# axiom_beta_plugin_module_3xmDP_v1_1_077a.net
KiCad netlist of a schematic drawn in EAGLE
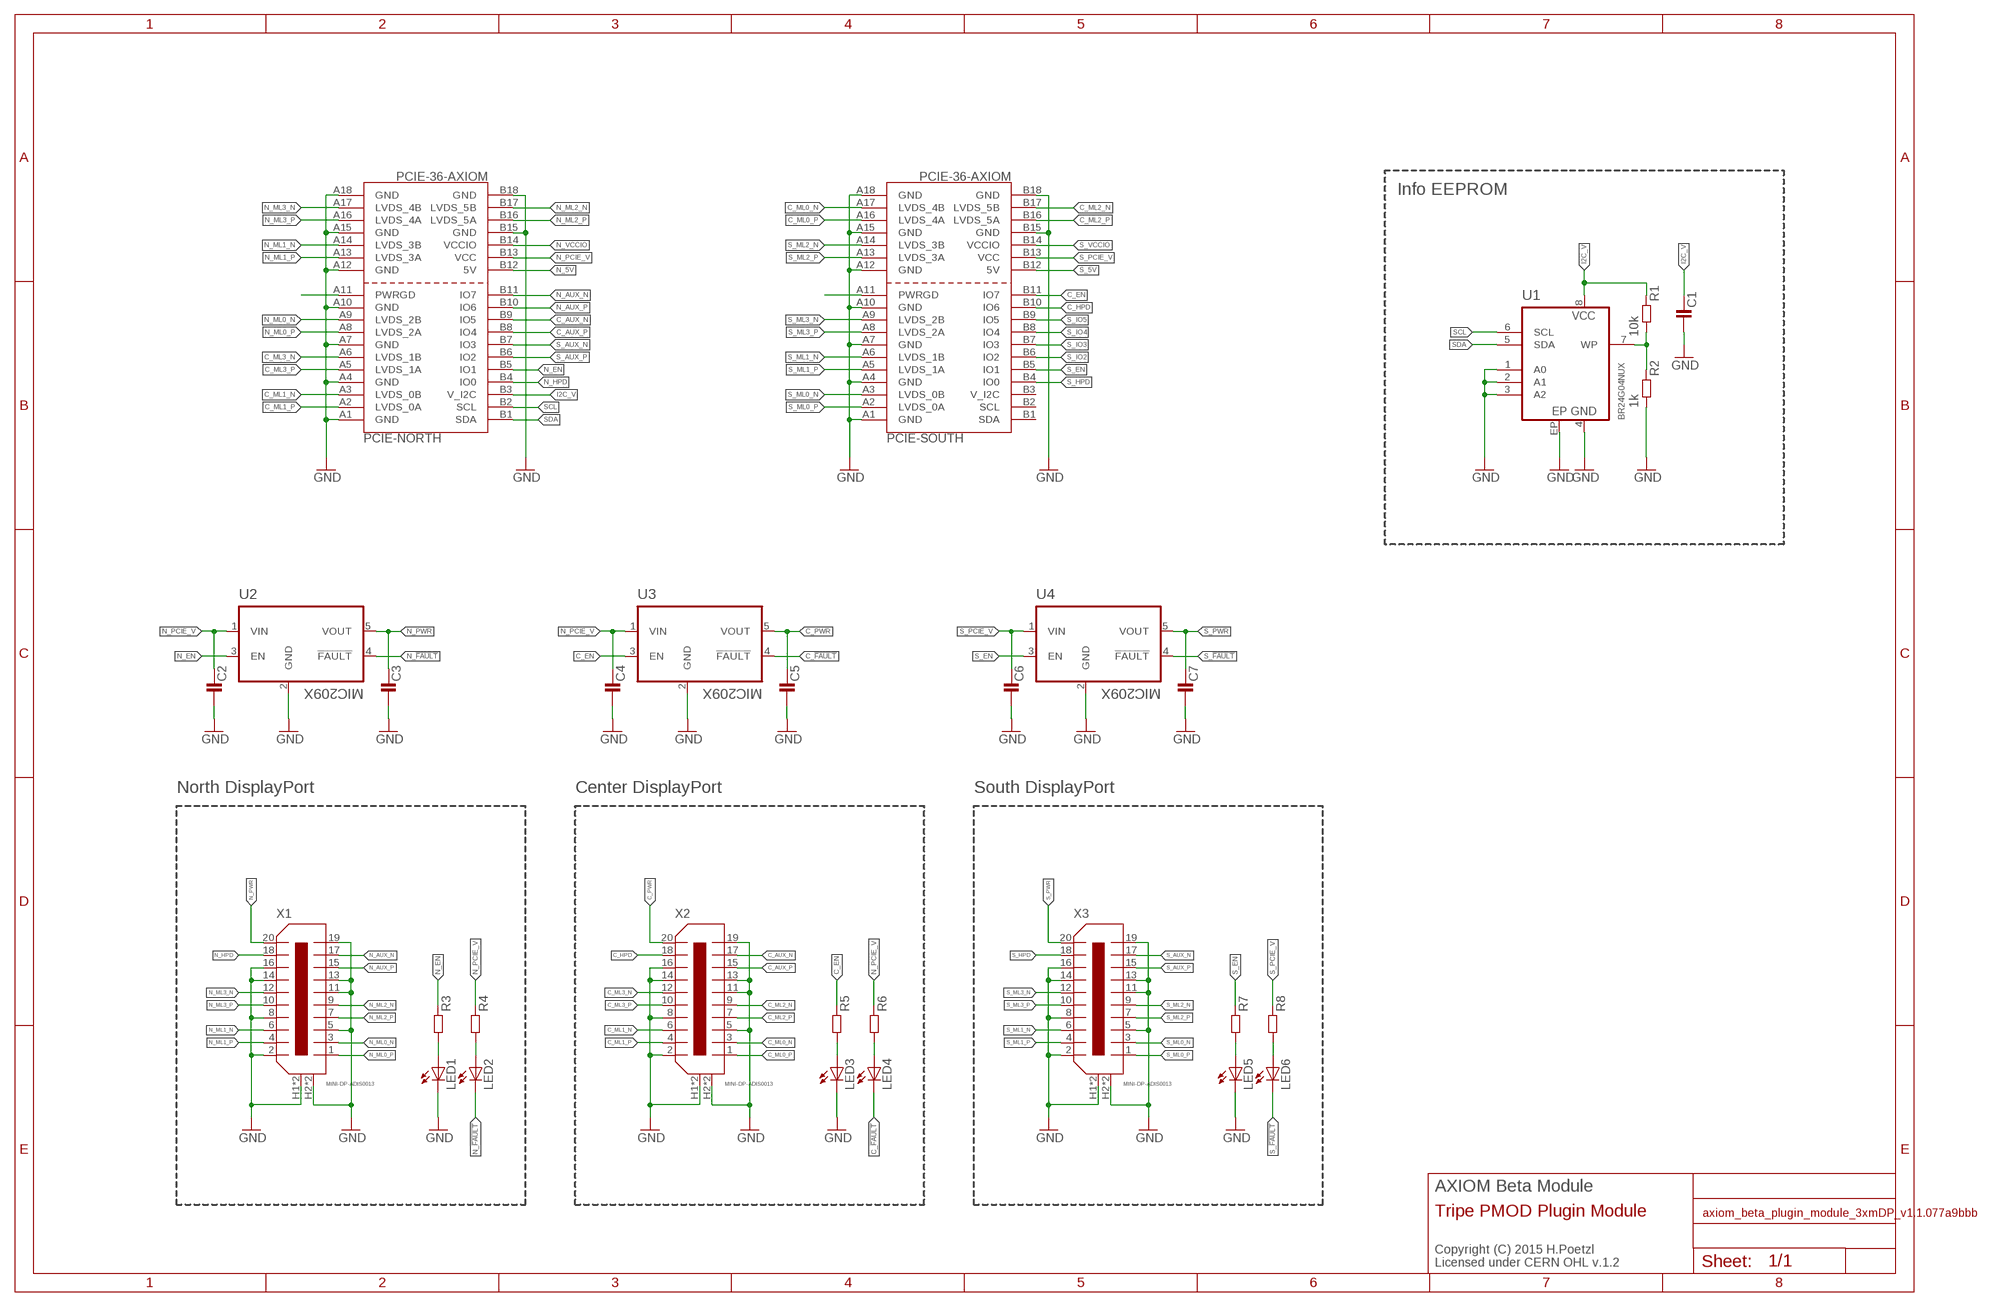
[diagram p0: schematic, sheet 1]

(export (version "E")
  (design (tool "Eeschema 10.0.6"))
  (components
    (comp (ref "C1")
      (value "C0402-B")
      (footprint "eagle-import:0402-B")
      (libsource (lib "eagle-import") (part "C0402-B"))
    )
    (comp (ref "C2")
      (value "C0603-B")
      (footprint "eagle-import:0603-B")
      (libsource (lib "eagle-import") (part "C0603-B"))
    )
    (comp (ref "C3")
      (value "C0603-B")
      (footprint "eagle-import:0603-B")
      (libsource (lib "eagle-import") (part "C0603-B"))
    )
    (comp (ref "C4")
      (value "C0603-B")
      (footprint "eagle-import:0603-B")
      (libsource (lib "eagle-import") (part "C0603-B"))
    )
    (comp (ref "C5")
      (value "C0603-B")
      (footprint "eagle-import:0603-B")
      (libsource (lib "eagle-import") (part "C0603-B"))
    )
    (comp (ref "C6")
      (value "C0603-B")
      (footprint "eagle-import:0603-B")
      (libsource (lib "eagle-import") (part "C0603-B"))
    )
    (comp (ref "C7")
      (value "C0603-B")
      (footprint "eagle-import:0603-B")
      (libsource (lib "eagle-import") (part "C0603-B"))
    )
    (comp (ref "LED1")
      (value "LEDCHIPLED_0603")
      (footprint "eagle-import:CHIPLED_0603")
      (libsource (lib "eagle-import") (part "LEDCHIPLED_0603"))
    )
    (comp (ref "LED2")
      (value "LEDCHIPLED_0603")
      (footprint "eagle-import:CHIPLED_0603")
      (libsource (lib "eagle-import") (part "LEDCHIPLED_0603"))
    )
    (comp (ref "LED3")
      (value "LEDCHIPLED_0603")
      (footprint "eagle-import:CHIPLED_0603")
      (libsource (lib "eagle-import") (part "LEDCHIPLED_0603"))
    )
    (comp (ref "LED4")
      (value "LEDCHIPLED_0603")
      (footprint "eagle-import:CHIPLED_0603")
      (libsource (lib "eagle-import") (part "LEDCHIPLED_0603"))
    )
    (comp (ref "LED5")
      (value "LEDCHIPLED_0603")
      (footprint "eagle-import:CHIPLED_0603")
      (libsource (lib "eagle-import") (part "LEDCHIPLED_0603"))
    )
    (comp (ref "LED6")
      (value "LEDCHIPLED_0603")
      (footprint "eagle-import:CHIPLED_0603")
      (libsource (lib "eagle-import") (part "LEDCHIPLED_0603"))
    )
    (comp (ref "PCIE-NORTH")
      (value "PCIE-36-AXIOM")
      (footprint "eagle-import:PCIE-36-AXIOM")
      (libsource (lib "eagle-import") (part "PCIE-36-AXIOM"))
    )
    (comp (ref "PCIE-SOUTH")
      (value "PCIE-36-AXIOM")
      (footprint "eagle-import:PCIE-36-AXIOM")
      (libsource (lib "eagle-import") (part "PCIE-36-AXIOM"))
    )
    (comp (ref "R1")
      (value "10k")
      (footprint "eagle-import:0402-B")
      (libsource (lib "eagle-import") (part "R0402-B"))
    )
    (comp (ref "R2")
      (value "1k")
      (footprint "eagle-import:0402-B")
      (libsource (lib "eagle-import") (part "R0402-B"))
    )
    (comp (ref "R3")
      (value "R0402-B")
      (footprint "eagle-import:0402-B")
      (libsource (lib "eagle-import") (part "R0402-B"))
    )
    (comp (ref "R4")
      (value "R0402-B")
      (footprint "eagle-import:0402-B")
      (libsource (lib "eagle-import") (part "R0402-B"))
    )
    (comp (ref "R5")
      (value "R0402-B")
      (footprint "eagle-import:0402-B")
      (libsource (lib "eagle-import") (part "R0402-B"))
    )
    (comp (ref "R6")
      (value "R0402-B")
      (footprint "eagle-import:0402-B")
      (libsource (lib "eagle-import") (part "R0402-B"))
    )
    (comp (ref "R7")
      (value "R0402-B")
      (footprint "eagle-import:0402-B")
      (libsource (lib "eagle-import") (part "R0402-B"))
    )
    (comp (ref "R8")
      (value "R0402-B")
      (footprint "eagle-import:0402-B")
      (libsource (lib "eagle-import") (part "R0402-B"))
    )
    (comp (ref "U1")
      (value "BR24G04NUX")
      (footprint "eagle-import:DFN200X300X100-9N")
      (libsource (lib "eagle-import") (part "BR24G04NUX"))
    )
    (comp (ref "U2")
      (value "MIC209X")
      (footprint "eagle-import:SOT95P280X145-5N")
      (fields (field (name "MPN") "MIC2090-1YM5TR"))
      (libsource (lib "eagle-import") (part "MIC209X"))
    )
    (comp (ref "U3")
      (value "MIC209X")
      (footprint "eagle-import:SOT95P280X145-5N")
      (fields (field (name "MPN") "MIC2090-1YM5TR"))
      (libsource (lib "eagle-import") (part "MIC209X"))
    )
    (comp (ref "U4")
      (value "MIC209X")
      (footprint "eagle-import:SOT95P280X145-5N")
      (fields (field (name "MPN") "MIC2090-1YM5TR"))
      (libsource (lib "eagle-import") (part "MIC209X"))
    )
    (comp (ref "X1")
      (value "MINI-DP-ADIS0013")
      (footprint "eagle-import:ADIS0013")
      (libsource (lib "eagle-import") (part "MINI-DP-ADIS0013"))
    )
    (comp (ref "X2")
      (value "MINI-DP-ADIS0013")
      (footprint "eagle-import:ADIS0013")
      (libsource (lib "eagle-import") (part "MINI-DP-ADIS0013"))
    )
    (comp (ref "X3")
      (value "MINI-DP-ADIS0013")
      (footprint "eagle-import:ADIS0013")
      (libsource (lib "eagle-import") (part "MINI-DP-ADIS0013"))
    )
  )
  (nets
    (net (code "1") (name "/C_~{FAULT}") (class "Default")
      (node (ref "LED4") (pin "C") (pinfunction "C_C") (pintype "passive"))
      (node (ref "U3") (pin "4") (pinfunction "~{FAULT}_4") (pintype "output"))
    )
    (net (code "2") (name "/N_~{FAULT}") (class "Default")
      (node (ref "LED2") (pin "C") (pinfunction "C_C") (pintype "passive"))
      (node (ref "U2") (pin "4") (pinfunction "~{FAULT}_4") (pintype "output"))
    )
    (net (code "3") (name "/S_~{FAULT}") (class "Default")
      (node (ref "LED6") (pin "C") (pinfunction "C_C") (pintype "passive"))
      (node (ref "U4") (pin "4") (pinfunction "~{FAULT}_4") (pintype "output"))
    )
    (net (code "4") (name "C_AUX_N") (class "Default")
      (node (ref "PCIE-NORTH") (pin "B9") (pinfunction "IO5_B9") (pintype "passive"))
      (node (ref "X2") (pin "17") (pinfunction "17_17") (pintype "passive"))
    )
    (net (code "5") (name "C_AUX_P") (class "Default")
      (node (ref "PCIE-NORTH") (pin "B8") (pinfunction "IO4_B8") (pintype "passive"))
      (node (ref "X2") (pin "15") (pinfunction "15_15") (pintype "passive"))
    )
    (net (code "6") (name "C_EN") (class "Default")
      (node (ref "PCIE-SOUTH") (pin "B11") (pinfunction "IO7_B11") (pintype "passive"))
      (node (ref "R5") (pin "1") (pinfunction "1_1") (pintype "passive"))
      (node (ref "U3") (pin "3") (pinfunction "EN_3") (pintype "input"))
    )
    (net (code "7") (name "C_HPD") (class "Default")
      (node (ref "PCIE-SOUTH") (pin "B10") (pinfunction "IO6_B10") (pintype "passive"))
      (node (ref "X2") (pin "18") (pinfunction "18_18") (pintype "passive"))
    )
    (net (code "8") (name "C_ML0_N") (class "Default")
      (node (ref "PCIE-SOUTH") (pin "A17") (pinfunction "LVDS_4B_A17") (pintype "passive"))
      (node (ref "X2") (pin "3") (pinfunction "3_3") (pintype "passive"))
    )
    (net (code "9") (name "C_ML0_P") (class "Default")
      (node (ref "PCIE-SOUTH") (pin "A16") (pinfunction "LVDS_4A_A16") (pintype "passive"))
      (node (ref "X2") (pin "1") (pinfunction "1_1") (pintype "passive"))
    )
    (net (code "10") (name "C_ML1_N") (class "Default")
      (node (ref "PCIE-NORTH") (pin "A3") (pinfunction "LVDS_0B_A3") (pintype "passive"))
      (node (ref "X2") (pin "6") (pinfunction "6_6") (pintype "passive"))
    )
    (net (code "11") (name "C_ML1_P") (class "Default")
      (node (ref "PCIE-NORTH") (pin "A2") (pinfunction "LVDS_0A_A2") (pintype "passive"))
      (node (ref "X2") (pin "4") (pinfunction "4_4") (pintype "passive"))
    )
    (net (code "12") (name "C_ML2_N") (class "Default")
      (node (ref "PCIE-SOUTH") (pin "B17") (pinfunction "LVDS_5B_B17") (pintype "passive"))
      (node (ref "X2") (pin "9") (pinfunction "9_9") (pintype "passive"))
    )
    (net (code "13") (name "C_ML2_P") (class "Default")
      (node (ref "PCIE-SOUTH") (pin "B16") (pinfunction "LVDS_5A_B16") (pintype "passive"))
      (node (ref "X2") (pin "7") (pinfunction "7_7") (pintype "passive"))
    )
    (net (code "14") (name "C_ML3_N") (class "Default")
      (node (ref "PCIE-NORTH") (pin "A6") (pinfunction "LVDS_1B_A6") (pintype "passive"))
      (node (ref "X2") (pin "12") (pinfunction "12_12") (pintype "passive"))
    )
    (net (code "15") (name "C_ML3_P") (class "Default")
      (node (ref "PCIE-NORTH") (pin "A5") (pinfunction "LVDS_1A_A5") (pintype "passive"))
      (node (ref "X2") (pin "10") (pinfunction "10_10") (pintype "passive"))
    )
    (net (code "16") (name "C_PWR") (class "Default")
      (node (ref "C5") (pin "1") (pinfunction "1_1") (pintype "passive"))
      (node (ref "U3") (pin "5") (pinfunction "VOUT_5") (pintype "output"))
      (node (ref "X2") (pin "20") (pinfunction "20_20") (pintype "passive"))
    )
    (net (code "17") (name "GND") (class "Default")
      (node (ref "C1") (pin "2") (pinfunction "2_2") (pintype "passive"))
      (node (ref "C2") (pin "2") (pinfunction "2_2") (pintype "passive"))
      (node (ref "C3") (pin "2") (pinfunction "2_2") (pintype "passive"))
      (node (ref "C4") (pin "2") (pinfunction "2_2") (pintype "passive"))
      (node (ref "C5") (pin "2") (pinfunction "2_2") (pintype "passive"))
      (node (ref "C6") (pin "2") (pinfunction "2_2") (pintype "passive"))
      (node (ref "C7") (pin "2") (pinfunction "2_2") (pintype "passive"))
      (node (ref "LED1") (pin "C") (pinfunction "C_C") (pintype "passive"))
      (node (ref "LED3") (pin "C") (pinfunction "C_C") (pintype "passive"))
      (node (ref "LED5") (pin "C") (pinfunction "C_C") (pintype "passive"))
      (node (ref "PCIE-NORTH") (pin "A1") (pinfunction "GND_A1") (pintype "passive"))
      (node (ref "PCIE-NORTH") (pin "A10") (pinfunction "GND_A10") (pintype "passive"))
      (node (ref "PCIE-NORTH") (pin "A12") (pinfunction "GND_A12") (pintype "passive"))
      (node (ref "PCIE-NORTH") (pin "A15") (pinfunction "GND_A15") (pintype "passive"))
      (node (ref "PCIE-NORTH") (pin "A18") (pinfunction "GND_A18") (pintype "passive"))
      (node (ref "PCIE-NORTH") (pin "A4") (pinfunction "GND_A4") (pintype "passive"))
      (node (ref "PCIE-NORTH") (pin "A7") (pinfunction "GND_A7") (pintype "passive"))
      (node (ref "PCIE-NORTH") (pin "B15") (pinfunction "GND_B15") (pintype "passive"))
      (node (ref "PCIE-NORTH") (pin "B18") (pinfunction "GND_B18") (pintype "passive"))
      (node (ref "PCIE-SOUTH") (pin "A1") (pinfunction "GND_A1") (pintype "passive"))
      (node (ref "PCIE-SOUTH") (pin "A10") (pinfunction "GND_A10") (pintype "passive"))
      (node (ref "PCIE-SOUTH") (pin "A12") (pinfunction "GND_A12") (pintype "passive"))
      (node (ref "PCIE-SOUTH") (pin "A15") (pinfunction "GND_A15") (pintype "passive"))
      (node (ref "PCIE-SOUTH") (pin "A18") (pinfunction "GND_A18") (pintype "passive"))
      (node (ref "PCIE-SOUTH") (pin "A4") (pinfunction "GND_A4") (pintype "passive"))
      (node (ref "PCIE-SOUTH") (pin "A7") (pinfunction "GND_A7") (pintype "passive"))
      (node (ref "PCIE-SOUTH") (pin "B15") (pinfunction "GND_B15") (pintype "passive"))
      (node (ref "PCIE-SOUTH") (pin "B18") (pinfunction "GND_B18") (pintype "passive"))
      (node (ref "R2") (pin "2") (pinfunction "2_2") (pintype "passive"))
      (node (ref "U1") (pin "1") (pinfunction "A0_1") (pintype "input"))
      (node (ref "U1") (pin "2") (pinfunction "A1_2") (pintype "input"))
      (node (ref "U1") (pin "3") (pinfunction "A2_3") (pintype "input"))
      (node (ref "U1") (pin "4") (pinfunction "GND_4") (pintype "passive"))
      (node (ref "U1") (pin "EP") (pinfunction "EP_EP") (pintype "passive"))
      (node (ref "U2") (pin "2") (pinfunction "GND_2") (pintype "passive"))
      (node (ref "U3") (pin "2") (pinfunction "GND_2") (pintype "passive"))
      (node (ref "U4") (pin "2") (pinfunction "GND_2") (pintype "passive"))
      (node (ref "X1") (pin "11") (pinfunction "11_11") (pintype "passive"))
      (node (ref "X1") (pin "13") (pinfunction "13_13") (pintype "passive"))
      (node (ref "X1") (pin "14") (pinfunction "14_14") (pintype "passive"))
      (node (ref "X1") (pin "16") (pinfunction "16_16") (pintype "passive"))
      (node (ref "X1") (pin "19") (pinfunction "19_19") (pintype "passive"))
      (node (ref "X1") (pin "2") (pinfunction "2_2") (pintype "passive"))
      (node (ref "X1") (pin "5") (pinfunction "5_5") (pintype "passive"))
      (node (ref "X1") (pin "8") (pinfunction "8_8") (pintype "passive"))
      (node (ref "X1") (pin "H1") (pinfunction "M_H1") (pintype "input"))
      (node (ref "X1") (pin "H2") (pinfunction "M_H2") (pintype "input"))
      (node (ref "X1") (pin "H3") (pinfunction "M_H3") (pintype "input"))
      (node (ref "X1") (pin "H4") (pinfunction "M_H4") (pintype "input"))
      (node (ref "X2") (pin "11") (pinfunction "11_11") (pintype "passive"))
      (node (ref "X2") (pin "13") (pinfunction "13_13") (pintype "passive"))
      (node (ref "X2") (pin "14") (pinfunction "14_14") (pintype "passive"))
      (node (ref "X2") (pin "16") (pinfunction "16_16") (pintype "passive"))
      (node (ref "X2") (pin "19") (pinfunction "19_19") (pintype "passive"))
      (node (ref "X2") (pin "2") (pinfunction "2_2") (pintype "passive"))
      (node (ref "X2") (pin "5") (pinfunction "5_5") (pintype "passive"))
      (node (ref "X2") (pin "8") (pinfunction "8_8") (pintype "passive"))
      (node (ref "X2") (pin "H1") (pinfunction "M_H1") (pintype "input"))
      (node (ref "X2") (pin "H2") (pinfunction "M_H2") (pintype "input"))
      (node (ref "X2") (pin "H3") (pinfunction "M_H3") (pintype "input"))
      (node (ref "X2") (pin "H4") (pinfunction "M_H4") (pintype "input"))
      (node (ref "X3") (pin "11") (pinfunction "11_11") (pintype "passive"))
      (node (ref "X3") (pin "13") (pinfunction "13_13") (pintype "passive"))
      (node (ref "X3") (pin "14") (pinfunction "14_14") (pintype "passive"))
      (node (ref "X3") (pin "16") (pinfunction "16_16") (pintype "passive"))
      (node (ref "X3") (pin "19") (pinfunction "19_19") (pintype "passive"))
      (node (ref "X3") (pin "2") (pinfunction "2_2") (pintype "passive"))
      (node (ref "X3") (pin "5") (pinfunction "5_5") (pintype "passive"))
      (node (ref "X3") (pin "8") (pinfunction "8_8") (pintype "passive"))
      (node (ref "X3") (pin "H1") (pinfunction "M_H1") (pintype "input"))
      (node (ref "X3") (pin "H2") (pinfunction "M_H2") (pintype "input"))
      (node (ref "X3") (pin "H3") (pinfunction "M_H3") (pintype "input"))
      (node (ref "X3") (pin "H4") (pinfunction "M_H4") (pintype "input"))
    )
    (net (code "18") (name "I2C_V") (class "Default")
      (node (ref "C1") (pin "1") (pinfunction "1_1") (pintype "passive"))
      (node (ref "PCIE-NORTH") (pin "B3") (pinfunction "V_I2C_B3") (pintype "passive"))
      (node (ref "R1") (pin "1") (pinfunction "1_1") (pintype "passive"))
      (node (ref "U1") (pin "8") (pinfunction "VCC_8") (pintype "power_in"))
    )
    (net (code "19") (name "N_5V") (class "Default")
      (node (ref "PCIE-NORTH") (pin "B12") (pinfunction "5V_B12") (pintype "passive"))
    )
    (net (code "20") (name "N_AUX_N") (class "Default")
      (node (ref "PCIE-NORTH") (pin "B11") (pinfunction "IO7_B11") (pintype "passive"))
      (node (ref "X1") (pin "17") (pinfunction "17_17") (pintype "passive"))
    )
    (net (code "21") (name "N_AUX_P") (class "Default")
      (node (ref "PCIE-NORTH") (pin "B10") (pinfunction "IO6_B10") (pintype "passive"))
      (node (ref "X1") (pin "15") (pinfunction "15_15") (pintype "passive"))
    )
    (net (code "22") (name "N_EN") (class "Default")
      (node (ref "PCIE-NORTH") (pin "B5") (pinfunction "IO1_B5") (pintype "passive"))
      (node (ref "R3") (pin "1") (pinfunction "1_1") (pintype "passive"))
      (node (ref "U2") (pin "3") (pinfunction "EN_3") (pintype "input"))
    )
    (net (code "23") (name "N_HPD") (class "Default")
      (node (ref "PCIE-NORTH") (pin "B4") (pinfunction "IO0_B4") (pintype "passive"))
      (node (ref "X1") (pin "18") (pinfunction "18_18") (pintype "passive"))
    )
    (net (code "24") (name "N_ML0_N") (class "Default")
      (node (ref "PCIE-NORTH") (pin "A9") (pinfunction "LVDS_2B_A9") (pintype "passive"))
      (node (ref "X1") (pin "3") (pinfunction "3_3") (pintype "passive"))
    )
    (net (code "25") (name "N_ML0_P") (class "Default")
      (node (ref "PCIE-NORTH") (pin "A8") (pinfunction "LVDS_2A_A8") (pintype "passive"))
      (node (ref "X1") (pin "1") (pinfunction "1_1") (pintype "passive"))
    )
    (net (code "26") (name "N_ML1_N") (class "Default")
      (node (ref "PCIE-NORTH") (pin "A14") (pinfunction "LVDS_3B_A14") (pintype "passive"))
      (node (ref "X1") (pin "6") (pinfunction "6_6") (pintype "passive"))
    )
    (net (code "27") (name "N_ML1_P") (class "Default")
      (node (ref "PCIE-NORTH") (pin "A13") (pinfunction "LVDS_3A_A13") (pintype "passive"))
      (node (ref "X1") (pin "4") (pinfunction "4_4") (pintype "passive"))
    )
    (net (code "28") (name "N_ML2_N") (class "Default")
      (node (ref "PCIE-NORTH") (pin "B17") (pinfunction "LVDS_5B_B17") (pintype "passive"))
      (node (ref "X1") (pin "9") (pinfunction "9_9") (pintype "passive"))
    )
    (net (code "29") (name "N_ML2_P") (class "Default")
      (node (ref "PCIE-NORTH") (pin "B16") (pinfunction "LVDS_5A_B16") (pintype "passive"))
      (node (ref "X1") (pin "7") (pinfunction "7_7") (pintype "passive"))
    )
    (net (code "30") (name "N_ML3_N") (class "Default")
      (node (ref "PCIE-NORTH") (pin "A17") (pinfunction "LVDS_4B_A17") (pintype "passive"))
      (node (ref "X1") (pin "12") (pinfunction "12_12") (pintype "passive"))
    )
    (net (code "31") (name "N_ML3_P") (class "Default")
      (node (ref "PCIE-NORTH") (pin "A16") (pinfunction "LVDS_4A_A16") (pintype "passive"))
      (node (ref "X1") (pin "10") (pinfunction "10_10") (pintype "passive"))
    )
    (net (code "32") (name "N_PCIE_V") (class "Default")
      (node (ref "C2") (pin "1") (pinfunction "1_1") (pintype "passive"))
      (node (ref "C4") (pin "1") (pinfunction "1_1") (pintype "passive"))
      (node (ref "PCIE-NORTH") (pin "B13") (pinfunction "VCC_B13") (pintype "passive"))
      (node (ref "R4") (pin "1") (pinfunction "1_1") (pintype "passive"))
      (node (ref "R6") (pin "1") (pinfunction "1_1") (pintype "passive"))
      (node (ref "U2") (pin "1") (pinfunction "VIN_1") (pintype "input"))
      (node (ref "U3") (pin "1") (pinfunction "VIN_1") (pintype "input"))
    )
    (net (code "33") (name "N_PWR") (class "Default")
      (node (ref "C3") (pin "1") (pinfunction "1_1") (pintype "passive"))
      (node (ref "U2") (pin "5") (pinfunction "VOUT_5") (pintype "output"))
      (node (ref "X1") (pin "20") (pinfunction "20_20") (pintype "passive"))
    )
    (net (code "34") (name "N_VCCIO") (class "Default")
      (node (ref "PCIE-NORTH") (pin "B14") (pinfunction "VCCIO_B14") (pintype "passive"))
    )
    (net (code "35") (name "Net-(LED1-PadA)") (class "Default")
      (node (ref "LED1") (pin "A") (pinfunction "A_A") (pintype "passive"))
      (node (ref "R3") (pin "2") (pinfunction "2_2") (pintype "passive"))
    )
    (net (code "36") (name "Net-(LED2-PadA)") (class "Default")
      (node (ref "LED2") (pin "A") (pinfunction "A_A") (pintype "passive"))
      (node (ref "R4") (pin "2") (pinfunction "2_2") (pintype "passive"))
    )
    (net (code "37") (name "Net-(LED3-PadA)") (class "Default")
      (node (ref "LED3") (pin "A") (pinfunction "A_A") (pintype "passive"))
      (node (ref "R5") (pin "2") (pinfunction "2_2") (pintype "passive"))
    )
    (net (code "38") (name "Net-(LED4-PadA)") (class "Default")
      (node (ref "LED4") (pin "A") (pinfunction "A_A") (pintype "passive"))
      (node (ref "R6") (pin "2") (pinfunction "2_2") (pintype "passive"))
    )
    (net (code "39") (name "Net-(LED5-PadA)") (class "Default")
      (node (ref "LED5") (pin "A") (pinfunction "A_A") (pintype "passive"))
      (node (ref "R7") (pin "2") (pinfunction "2_2") (pintype "passive"))
    )
    (net (code "40") (name "Net-(LED6-PadA)") (class "Default")
      (node (ref "LED6") (pin "A") (pinfunction "A_A") (pintype "passive"))
      (node (ref "R8") (pin "2") (pinfunction "2_2") (pintype "passive"))
    )
    (net (code "41") (name "Net-(U1-WP)") (class "Default")
      (node (ref "R1") (pin "2") (pinfunction "2_2") (pintype "passive"))
      (node (ref "R2") (pin "1") (pinfunction "1_1") (pintype "passive"))
      (node (ref "U1") (pin "7") (pinfunction "WP_7") (pintype "input"))
    )
    (net (code "42") (name "SCL") (class "Default")
      (node (ref "PCIE-NORTH") (pin "B2") (pinfunction "SCL_B2") (pintype "passive"))
      (node (ref "U1") (pin "6") (pinfunction "SCL_6") (pintype "input"))
    )
    (net (code "43") (name "SDA") (class "Default")
      (node (ref "PCIE-NORTH") (pin "B1") (pinfunction "SDA_B1") (pintype "passive"))
      (node (ref "U1") (pin "5") (pinfunction "SDA_5") (pintype "bidirectional"))
    )
    (net (code "44") (name "S_5V") (class "Default")
      (node (ref "PCIE-SOUTH") (pin "B12") (pinfunction "5V_B12") (pintype "passive"))
    )
    (net (code "45") (name "S_AUX_N") (class "Default")
      (node (ref "PCIE-NORTH") (pin "B7") (pinfunction "IO3_B7") (pintype "passive"))
      (node (ref "X3") (pin "17") (pinfunction "17_17") (pintype "passive"))
    )
    (net (code "46") (name "S_AUX_P") (class "Default")
      (node (ref "PCIE-NORTH") (pin "B6") (pinfunction "IO2_B6") (pintype "passive"))
      (node (ref "X3") (pin "15") (pinfunction "15_15") (pintype "passive"))
    )
    (net (code "47") (name "S_EN") (class "Default")
      (node (ref "PCIE-SOUTH") (pin "B5") (pinfunction "IO1_B5") (pintype "passive"))
      (node (ref "R7") (pin "1") (pinfunction "1_1") (pintype "passive"))
      (node (ref "U4") (pin "3") (pinfunction "EN_3") (pintype "input"))
    )
    (net (code "48") (name "S_HPD") (class "Default")
      (node (ref "PCIE-SOUTH") (pin "B4") (pinfunction "IO0_B4") (pintype "passive"))
      (node (ref "X3") (pin "18") (pinfunction "18_18") (pintype "passive"))
    )
    (net (code "49") (name "S_IO2") (class "Default")
      (node (ref "PCIE-SOUTH") (pin "B6") (pinfunction "IO2_B6") (pintype "passive"))
    )
    (net (code "50") (name "S_IO3") (class "Default")
      (node (ref "PCIE-SOUTH") (pin "B7") (pinfunction "IO3_B7") (pintype "passive"))
    )
    (net (code "51") (name "S_IO4") (class "Default")
      (node (ref "PCIE-SOUTH") (pin "B8") (pinfunction "IO4_B8") (pintype "passive"))
    )
    (net (code "52") (name "S_IO5") (class "Default")
      (node (ref "PCIE-SOUTH") (pin "B9") (pinfunction "IO5_B9") (pintype "passive"))
    )
    (net (code "53") (name "S_ML0_N") (class "Default")
      (node (ref "PCIE-SOUTH") (pin "A3") (pinfunction "LVDS_0B_A3") (pintype "passive"))
      (node (ref "X3") (pin "3") (pinfunction "3_3") (pintype "passive"))
    )
    (net (code "54") (name "S_ML0_P") (class "Default")
      (node (ref "PCIE-SOUTH") (pin "A2") (pinfunction "LVDS_0A_A2") (pintype "passive"))
      (node (ref "X3") (pin "1") (pinfunction "1_1") (pintype "passive"))
    )
    (net (code "55") (name "S_ML1_N") (class "Default")
      (node (ref "PCIE-SOUTH") (pin "A6") (pinfunction "LVDS_1B_A6") (pintype "passive"))
      (node (ref "X3") (pin "6") (pinfunction "6_6") (pintype "passive"))
    )
    (net (code "56") (name "S_ML1_P") (class "Default")
      (node (ref "PCIE-SOUTH") (pin "A5") (pinfunction "LVDS_1A_A5") (pintype "passive"))
      (node (ref "X3") (pin "4") (pinfunction "4_4") (pintype "passive"))
    )
    (net (code "57") (name "S_ML2_N") (class "Default")
      (node (ref "PCIE-SOUTH") (pin "A14") (pinfunction "LVDS_3B_A14") (pintype "passive"))
      (node (ref "X3") (pin "9") (pinfunction "9_9") (pintype "passive"))
    )
    (net (code "58") (name "S_ML2_P") (class "Default")
      (node (ref "PCIE-SOUTH") (pin "A13") (pinfunction "LVDS_3A_A13") (pintype "passive"))
      (node (ref "X3") (pin "7") (pinfunction "7_7") (pintype "passive"))
    )
    (net (code "59") (name "S_ML3_N") (class "Default")
      (node (ref "PCIE-SOUTH") (pin "A9") (pinfunction "LVDS_2B_A9") (pintype "passive"))
      (node (ref "X3") (pin "12") (pinfunction "12_12") (pintype "passive"))
    )
    (net (code "60") (name "S_ML3_P") (class "Default")
      (node (ref "PCIE-SOUTH") (pin "A8") (pinfunction "LVDS_2A_A8") (pintype "passive"))
      (node (ref "X3") (pin "10") (pinfunction "10_10") (pintype "passive"))
    )
    (net (code "61") (name "S_PCIE_V") (class "Default")
      (node (ref "C6") (pin "1") (pinfunction "1_1") (pintype "passive"))
      (node (ref "PCIE-SOUTH") (pin "B13") (pinfunction "VCC_B13") (pintype "passive"))
      (node (ref "R8") (pin "1") (pinfunction "1_1") (pintype "passive"))
      (node (ref "U4") (pin "1") (pinfunction "VIN_1") (pintype "input"))
    )
    (net (code "62") (name "S_PWR") (class "Default")
      (node (ref "C7") (pin "1") (pinfunction "1_1") (pintype "passive"))
      (node (ref "U4") (pin "5") (pinfunction "VOUT_5") (pintype "output"))
      (node (ref "X3") (pin "20") (pinfunction "20_20") (pintype "passive"))
    )
    (net (code "63") (name "S_VCCIO") (class "Default")
      (node (ref "PCIE-SOUTH") (pin "B14") (pinfunction "VCCIO_B14") (pintype "passive"))
    )
    (net (code "64") (name "unconnected-(PCIE-NORTH-PWRGD-PadA11)") (class "Default")
      (node (ref "PCIE-NORTH") (pin "A11") (pinfunction "PWRGD_A11") (pintype "passive"))
    )
    (net (code "65") (name "unconnected-(PCIE-SOUTH-PWRGD-PadA11)") (class "Default")
      (node (ref "PCIE-SOUTH") (pin "A11") (pinfunction "PWRGD_A11") (pintype "passive"))
    )
    (net (code "66") (name "unconnected-(PCIE-SOUTH-SCL-PadB2)") (class "Default")
      (node (ref "PCIE-SOUTH") (pin "B2") (pinfunction "SCL_B2") (pintype "passive"))
    )
    (net (code "67") (name "unconnected-(PCIE-SOUTH-SDA-PadB1)") (class "Default")
      (node (ref "PCIE-SOUTH") (pin "B1") (pinfunction "SDA_B1") (pintype "passive"))
    )
    (net (code "68") (name "unconnected-(PCIE-SOUTH-V_I2C-PadB3)") (class "Default")
      (node (ref "PCIE-SOUTH") (pin "B3") (pinfunction "V_I2C_B3") (pintype "passive"))
    )
  )
)
